# BUS.net
KiCad netlist of a schematic drawn in Altium Designer
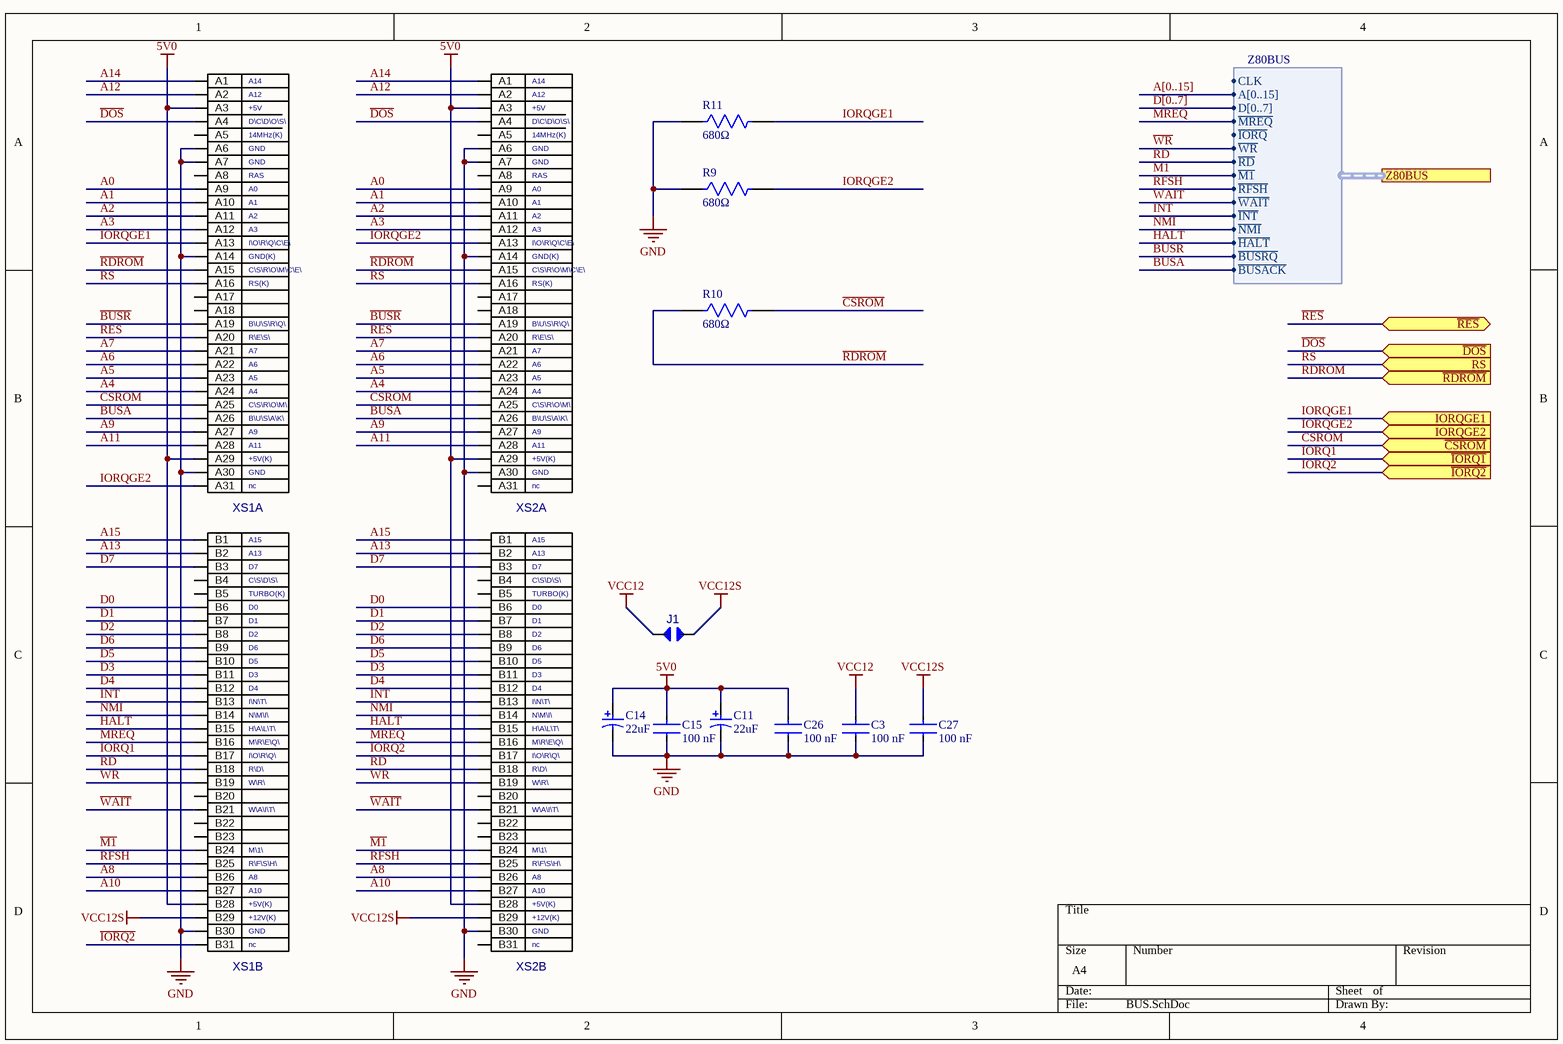
[diagram p0: BUS.SchDoc]

(export (version "E")
  (design (tool "Eeschema 10.0.6"))
  (components
    (comp (ref "C3")
      (value "CC0805KRX7R9BB104")
      (footprint "FP-CC0805-0_85-IPC_A")
      (description "CAP CER 0.1UF 50V X7R 0805")
      (fields (field (name "CAPACITANCE") "100 nF") (field (name "MANUFACTURER") "Yageo"))
      (libsource (lib "SchLib") (part "CMP-2100-03606-3"))
    )
    (comp (ref "C11")
      (value "TAJB226K016RNJ")
      (footprint "AVX-TAJ-B-2_M")
      (description "Standard Tantalum, 22 uF, +/- 10%, 16 V, -55 to 125 degC, 2-Pin SMD (1210), RoHS, Tape and Reel")
      (fields (field (name "CAPACITANCE") "22uF") (field (name "MANUFACTURER") "Kyocera AVX"))
      (libsource (lib "SchLib") (part "CMP-2100-03689-1"))
    )
    (comp (ref "C14")
      (value "TAJB226K016RNJ")
      (footprint "AVX-TAJ-B-2_M")
      (description "Standard Tantalum, 22 uF, +/- 10%, 16 V, -55 to 125 degC, 2-Pin SMD (1210), RoHS, Tape and Reel")
      (fields (field (name "CAPACITANCE") "22uF") (field (name "MANUFACTURER") "Kyocera AVX"))
      (libsource (lib "SchLib") (part "CMP-2100-03689-1"))
    )
    (comp (ref "C15")
      (value "CC0805KRX7R9BB104")
      (footprint "FP-CC0805-0_85-IPC_A")
      (description "CAP CER 0.1UF 50V X7R 0805")
      (fields (field (name "CAPACITANCE") "100 nF") (field (name "MANUFACTURER") "Yageo"))
      (libsource (lib "SchLib") (part "CMP-2100-03606-3"))
    )
    (comp (ref "C26")
      (value "CC0805KRX7R9BB104")
      (footprint "FP-CC0805-0_85-IPC_A")
      (description "CAP CER 0.1UF 50V X7R 0805")
      (fields (field (name "CAPACITANCE") "100 nF") (field (name "MANUFACTURER") "Yageo"))
      (libsource (lib "SchLib") (part "CMP-2100-03606-3"))
    )
    (comp (ref "C27")
      (value "CC0805KRX7R9BB104")
      (footprint "FP-CC0805-0_85-IPC_A")
      (description "CAP CER 0.1UF 50V X7R 0805")
      (fields (field (name "CAPACITANCE") "100 nF") (field (name "MANUFACTURER") "Yageo"))
      (libsource (lib "SchLib") (part "CMP-2100-03606-3"))
    )
    (comp (ref "J1")
      (value "JUMPER")
      (footprint "JUMPER_JUMPER(Primary)")
      (description "HLT->~IP")
      (libsource (lib "SchLib") (part "JUMPER"))
    )
    (comp (ref "R9")
      (value "680Ω")
      (footprint "FP-RT0805-IPC_A")
      (description "RES SMD 680 OHM 1% 1/8W 0805")
      (fields
        (field (name "MANUFACTURER") "Yageo")
        (field (name "MANUFACTURER PART NUMBER") "RT0805FRE07680RL")
      )
      (libsource (lib "SchLib") (part "CMP-03412-000082-1"))
    )
    (comp (ref "R10")
      (value "680Ω")
      (footprint "FP-RT0805-IPC_A")
      (description "RES SMD 680 OHM 1% 1/8W 0805")
      (fields
        (field (name "MANUFACTURER") "Yageo")
        (field (name "MANUFACTURER PART NUMBER") "RT0805FRE07680RL")
      )
      (libsource (lib "SchLib") (part "CMP-03412-000082-1"))
    )
    (comp (ref "R11")
      (value "680Ω")
      (footprint "FP-RT0805-IPC_A")
      (description "RES SMD 680 OHM 1% 1/8W 0805")
      (fields
        (field (name "MANUFACTURER") "Yageo")
        (field (name "MANUFACTURER PART NUMBER") "RT0805FRE07680RL")
      )
      (libsource (lib "SchLib") (part "CMP-03412-000082-1"))
    )
    (comp (ref "XS1")
      (value "ZXSLOT")
      (footprint "SLOT62_ZXSLOT(Primary)")
      (libsource (lib "SchLib") (part "ZXSLOT"))
    )
    (comp (ref "XS2")
      (value "ZXSLOT")
      (footprint "SLOT62_ZXSLOT(Primary)")
      (libsource (lib "SchLib") (part "ZXSLOT"))
    )
  )
  (nets
    (net (code "2") (name "/A0") (class "Default")
      (node (ref "XS1") (pin "A9") (pinfunction "A9_A9") (pintype "passive"))
      (node (ref "XS2") (pin "A9") (pinfunction "A9_A9") (pintype "passive"))
    )
    (net (code "3") (name "/A1") (class "Default")
      (node (ref "XS1") (pin "A10") (pinfunction "A10_A10") (pintype "passive"))
      (node (ref "XS2") (pin "A10") (pinfunction "A10_A10") (pintype "passive"))
    )
    (net (code "4") (name "/A2") (class "Default")
      (node (ref "XS1") (pin "A11") (pinfunction "A11_A11") (pintype "passive"))
      (node (ref "XS2") (pin "A11") (pinfunction "A11_A11") (pintype "passive"))
    )
    (net (code "5") (name "/A3") (class "Default")
      (node (ref "XS1") (pin "A12") (pinfunction "A12_A12") (pintype "passive"))
      (node (ref "XS2") (pin "A12") (pinfunction "A12_A12") (pintype "passive"))
    )
    (net (code "6") (name "/A4") (class "Default")
      (node (ref "XS1") (pin "A24") (pinfunction "A24_A24") (pintype "passive"))
      (node (ref "XS2") (pin "A24") (pinfunction "A24_A24") (pintype "passive"))
    )
    (net (code "7") (name "/A5") (class "Default")
      (node (ref "XS1") (pin "A23") (pinfunction "A23_A23") (pintype "passive"))
      (node (ref "XS2") (pin "A23") (pinfunction "A23_A23") (pintype "passive"))
    )
    (net (code "8") (name "/A6") (class "Default")
      (node (ref "XS1") (pin "A22") (pinfunction "A22_A22") (pintype "passive"))
      (node (ref "XS2") (pin "A22") (pinfunction "A22_A22") (pintype "passive"))
    )
    (net (code "9") (name "/A7") (class "Default")
      (node (ref "XS1") (pin "A21") (pinfunction "A21_A21") (pintype "passive"))
      (node (ref "XS2") (pin "A21") (pinfunction "A21_A21") (pintype "passive"))
    )
    (net (code "10") (name "/A8") (class "Default")
      (node (ref "XS1") (pin "B26") (pinfunction "B26_B26") (pintype "passive"))
      (node (ref "XS2") (pin "B26") (pinfunction "B26_B26") (pintype "passive"))
    )
    (net (code "11") (name "/A9") (class "Default")
      (node (ref "XS1") (pin "A27") (pinfunction "A27_A27") (pintype "passive"))
      (node (ref "XS2") (pin "A27") (pinfunction "A27_A27") (pintype "passive"))
    )
    (net (code "12") (name "/A10") (class "Default")
      (node (ref "XS1") (pin "B27") (pinfunction "B27_B27") (pintype "passive"))
      (node (ref "XS2") (pin "B27") (pinfunction "B27_B27") (pintype "passive"))
    )
    (net (code "13") (name "/A11") (class "Default")
      (node (ref "XS1") (pin "A28") (pinfunction "A28_A28") (pintype "passive"))
      (node (ref "XS2") (pin "A28") (pinfunction "A28_A28") (pintype "passive"))
    )
    (net (code "14") (name "/A12") (class "Default")
      (node (ref "XS1") (pin "A2") (pinfunction "A2_A2") (pintype "passive"))
      (node (ref "XS2") (pin "A2") (pinfunction "A2_A2") (pintype "passive"))
    )
    (net (code "15") (name "/A13") (class "Default")
      (node (ref "XS1") (pin "B2") (pinfunction "B2_B2") (pintype "passive"))
      (node (ref "XS2") (pin "B2") (pinfunction "B2_B2") (pintype "passive"))
    )
    (net (code "16") (name "/A14") (class "Default")
      (node (ref "XS1") (pin "A1") (pinfunction "A1_A1") (pintype "passive"))
      (node (ref "XS2") (pin "A1") (pinfunction "A1_A1") (pintype "passive"))
    )
    (net (code "17") (name "/A15") (class "Default")
      (node (ref "XS1") (pin "B1") (pinfunction "B1_B1") (pintype "passive"))
      (node (ref "XS2") (pin "B1") (pinfunction "B1_B1") (pintype "passive"))
    )
    (net (code "19") (name "/D0") (class "Default")
      (node (ref "XS1") (pin "B6") (pinfunction "B6_B6") (pintype "passive"))
      (node (ref "XS2") (pin "B6") (pinfunction "B6_B6") (pintype "passive"))
    )
    (net (code "20") (name "/D1") (class "Default")
      (node (ref "XS1") (pin "B7") (pinfunction "B7_B7") (pintype "passive"))
      (node (ref "XS2") (pin "B7") (pinfunction "B7_B7") (pintype "passive"))
    )
    (net (code "21") (name "/D2") (class "Default")
      (node (ref "XS1") (pin "B8") (pinfunction "B8_B8") (pintype "passive"))
      (node (ref "XS2") (pin "B8") (pinfunction "B8_B8") (pintype "passive"))
    )
    (net (code "22") (name "/D3") (class "Default")
      (node (ref "XS1") (pin "B11") (pinfunction "B11_B11") (pintype "passive"))
      (node (ref "XS2") (pin "B11") (pinfunction "B11_B11") (pintype "passive"))
    )
    (net (code "23") (name "/D4") (class "Default")
      (node (ref "XS1") (pin "B12") (pinfunction "B12_B12") (pintype "passive"))
      (node (ref "XS2") (pin "B12") (pinfunction "B12_B12") (pintype "passive"))
    )
    (net (code "24") (name "/D5") (class "Default")
      (node (ref "XS1") (pin "B10") (pinfunction "B10_B10") (pintype "passive"))
      (node (ref "XS2") (pin "B10") (pinfunction "B10_B10") (pintype "passive"))
    )
    (net (code "25") (name "/D6") (class "Default")
      (node (ref "XS1") (pin "B9") (pinfunction "B9_B9") (pintype "passive"))
      (node (ref "XS2") (pin "B9") (pinfunction "B9_B9") (pintype "passive"))
    )
    (net (code "26") (name "/D7") (class "Default")
      (node (ref "XS1") (pin "B3") (pinfunction "B3_B3") (pintype "passive"))
      (node (ref "XS2") (pin "B3") (pinfunction "B3_B3") (pintype "passive"))
    )
    (net (code "28") (name "/IORQGE1") (class "Default")
      (node (ref "R11") (pin "2") (pinfunction "2_2") (pintype "passive"))
      (node (ref "XS1") (pin "A13") (pinfunction "A13_A13") (pintype "passive"))
    )
    (net (code "29") (name "/IORQGE2") (class "Default")
      (node (ref "R9") (pin "2") (pinfunction "2_2") (pintype "passive"))
      (node (ref "XS1") (pin "A31") (pinfunction "A31_A31") (pintype "passive"))
      (node (ref "XS2") (pin "A13") (pinfunction "A13_A13") (pintype "passive"))
    )
    (net (code "30") (name "/RS") (class "Default")
      (node (ref "XS1") (pin "A16") (pinfunction "A16_A16") (pintype "passive"))
      (node (ref "XS2") (pin "A16") (pinfunction "A16_A16") (pintype "passive"))
    )
    (net (code "32") (name "/~{BUSA}") (class "Default")
      (node (ref "XS1") (pin "A26") (pinfunction "A26_A26") (pintype "passive"))
      (node (ref "XS2") (pin "A26") (pinfunction "A26_A26") (pintype "passive"))
    )
    (net (code "33") (name "/~{BUSR}") (class "Default")
      (node (ref "XS1") (pin "A19") (pinfunction "A19_A19") (pintype "passive"))
      (node (ref "XS2") (pin "A19") (pinfunction "A19_A19") (pintype "passive"))
    )
    (net (code "34") (name "/~{CSROM}") (class "Default")
      (node (ref "R10") (pin "2") (pinfunction "2_2") (pintype "passive"))
      (node (ref "XS1") (pin "A25") (pinfunction "A25_A25") (pintype "passive"))
      (node (ref "XS2") (pin "A25") (pinfunction "A25_A25") (pintype "passive"))
    )
    (net (code "35") (name "/~{DOS}") (class "Default")
      (node (ref "XS1") (pin "A4") (pinfunction "A4_A4") (pintype "passive"))
      (node (ref "XS2") (pin "A4") (pinfunction "A4_A4") (pintype "passive"))
    )
    (net (code "36") (name "/~{HALT}") (class "Default")
      (node (ref "XS1") (pin "B15") (pinfunction "B15_B15") (pintype "passive"))
      (node (ref "XS2") (pin "B15") (pinfunction "B15_B15") (pintype "passive"))
    )
    (net (code "37") (name "/~{INT}") (class "Default")
      (node (ref "XS1") (pin "B13") (pinfunction "B13_B13") (pintype "passive"))
      (node (ref "XS2") (pin "B13") (pinfunction "B13_B13") (pintype "passive"))
    )
    (net (code "38") (name "/~{IORQ1}") (class "Default")
      (node (ref "XS1") (pin "B17") (pinfunction "B17_B17") (pintype "passive"))
    )
    (net (code "39") (name "/~{IORQ2}") (class "Default")
      (node (ref "XS1") (pin "B31") (pinfunction "B31_B31") (pintype "passive"))
      (node (ref "XS2") (pin "B17") (pinfunction "B17_B17") (pintype "passive"))
    )
    (net (code "40") (name "/~{M1}") (class "Default")
      (node (ref "XS1") (pin "B24") (pinfunction "B24_B24") (pintype "passive"))
      (node (ref "XS2") (pin "B24") (pinfunction "B24_B24") (pintype "passive"))
    )
    (net (code "41") (name "/~{MREQ}") (class "Default")
      (node (ref "XS1") (pin "B16") (pinfunction "B16_B16") (pintype "passive"))
      (node (ref "XS2") (pin "B16") (pinfunction "B16_B16") (pintype "passive"))
    )
    (net (code "42") (name "/~{NMI}") (class "Default")
      (node (ref "XS1") (pin "B14") (pinfunction "B14_B14") (pintype "passive"))
      (node (ref "XS2") (pin "B14") (pinfunction "B14_B14") (pintype "passive"))
    )
    (net (code "43") (name "/~{RDROM}") (class "Default")
      (node (ref "R10") (pin "1") (pinfunction "1_1") (pintype "passive"))
      (node (ref "XS1") (pin "A15") (pinfunction "A15_A15") (pintype "passive"))
      (node (ref "XS2") (pin "A15") (pinfunction "A15_A15") (pintype "passive"))
    )
    (net (code "44") (name "/~{RD}") (class "Default")
      (node (ref "XS1") (pin "B18") (pinfunction "B18_B18") (pintype "passive"))
      (node (ref "XS2") (pin "B18") (pinfunction "B18_B18") (pintype "passive"))
    )
    (net (code "45") (name "/~{RES}") (class "Default")
      (node (ref "XS1") (pin "A20") (pinfunction "A20_A20") (pintype "passive"))
      (node (ref "XS2") (pin "A20") (pinfunction "A20_A20") (pintype "passive"))
    )
    (net (code "46") (name "/~{RFSH}") (class "Default")
      (node (ref "XS1") (pin "B25") (pinfunction "B25_B25") (pintype "passive"))
      (node (ref "XS2") (pin "B25") (pinfunction "B25_B25") (pintype "passive"))
    )
    (net (code "47") (name "/~{WAIT}") (class "Default")
      (node (ref "XS1") (pin "B21") (pinfunction "B21_B21") (pintype "passive"))
      (node (ref "XS2") (pin "B21") (pinfunction "B21_B21") (pintype "passive"))
    )
    (net (code "48") (name "/~{WR}") (class "Default")
      (node (ref "XS1") (pin "B19") (pinfunction "B19_B19") (pintype "passive"))
      (node (ref "XS2") (pin "B19") (pinfunction "B19_B19") (pintype "passive"))
    )
    (net (code "49") (name "5V0") (class "Default")
      (node (ref "C11") (pin "1") (pinfunction "1_1") (pintype "passive"))
      (node (ref "C14") (pin "1") (pinfunction "1_1") (pintype "passive"))
      (node (ref "C15") (pin "1") (pinfunction "1_1") (pintype "passive"))
      (node (ref "C26") (pin "1") (pinfunction "1_1") (pintype "passive"))
      (node (ref "XS1") (pin "A29") (pinfunction "A29_A29") (pintype "passive"))
      (node (ref "XS1") (pin "A3") (pinfunction "A3_A3") (pintype "passive"))
      (node (ref "XS1") (pin "B28") (pinfunction "B28_B28") (pintype "passive"))
      (node (ref "XS2") (pin "A29") (pinfunction "A29_A29") (pintype "passive"))
      (node (ref "XS2") (pin "A3") (pinfunction "A3_A3") (pintype "passive"))
      (node (ref "XS2") (pin "B28") (pinfunction "B28_B28") (pintype "passive"))
    )
    (net (code "50") (name "GND") (class "Default")
      (node (ref "C11") (pin "2") (pinfunction "2_2") (pintype "passive"))
      (node (ref "C14") (pin "2") (pinfunction "2_2") (pintype "passive"))
      (node (ref "C15") (pin "2") (pinfunction "2_2") (pintype "passive"))
      (node (ref "C26") (pin "2") (pinfunction "2_2") (pintype "passive"))
      (node (ref "C27") (pin "2") (pinfunction "2_2") (pintype "passive"))
      (node (ref "C3") (pin "2") (pinfunction "2_2") (pintype "passive"))
      (node (ref "R11") (pin "1") (pinfunction "1_1") (pintype "passive"))
      (node (ref "R9") (pin "1") (pinfunction "1_1") (pintype "passive"))
      (node (ref "XS1") (pin "A14") (pinfunction "A14_A14") (pintype "passive"))
      (node (ref "XS1") (pin "A30") (pinfunction "A30_A30") (pintype "passive"))
      (node (ref "XS1") (pin "A6") (pinfunction "A6_A6") (pintype "passive"))
      (node (ref "XS1") (pin "A7") (pinfunction "A7_A7") (pintype "passive"))
      (node (ref "XS1") (pin "B30") (pinfunction "B30_B30") (pintype "passive"))
      (node (ref "XS2") (pin "A14") (pinfunction "A14_A14") (pintype "passive"))
      (node (ref "XS2") (pin "A30") (pinfunction "A30_A30") (pintype "passive"))
      (node (ref "XS2") (pin "A6") (pinfunction "A6_A6") (pintype "passive"))
      (node (ref "XS2") (pin "A7") (pinfunction "A7_A7") (pintype "passive"))
      (node (ref "XS2") (pin "B30") (pinfunction "B30_B30") (pintype "passive"))
    )
    (net (code "51") (name "VCC12") (class "Default")
      (node (ref "C3") (pin "1") (pinfunction "1_1") (pintype "passive"))
      (node (ref "J1") (pin "0") (pinfunction "1_0") (pintype "passive"))
    )
    (net (code "52") (name "VCC12S") (class "Default")
      (node (ref "C27") (pin "1") (pinfunction "1_1") (pintype "passive"))
      (node (ref "J1") (pin "1") (pinfunction "2_1") (pintype "passive"))
      (node (ref "XS1") (pin "B29") (pinfunction "B29_B29") (pintype "passive"))
      (node (ref "XS2") (pin "B29") (pinfunction "B29_B29") (pintype "passive"))
    )
    (net (code "53") (name "unconnected-(XS1-PadA5)") (class "Default")
      (node (ref "XS1") (pin "A5") (pinfunction "A5_A5") (pintype "passive"))
    )
    (net (code "54") (name "unconnected-(XS1-PadA8)") (class "Default")
      (node (ref "XS1") (pin "A8") (pinfunction "A8_A8") (pintype "passive"))
    )
    (net (code "55") (name "unconnected-(XS1-PadA17)") (class "Default")
      (node (ref "XS1") (pin "A17") (pinfunction "A17_A17") (pintype "passive"))
    )
    (net (code "56") (name "unconnected-(XS1-PadA18)") (class "Default")
      (node (ref "XS1") (pin "A18") (pinfunction "A18_A18") (pintype "passive"))
    )
    (net (code "57") (name "unconnected-(XS1-PadB4)") (class "Default")
      (node (ref "XS1") (pin "B4") (pinfunction "B4_B4") (pintype "passive"))
    )
    (net (code "58") (name "unconnected-(XS1-PadB5)") (class "Default")
      (node (ref "XS1") (pin "B5") (pinfunction "B5_B5") (pintype "passive"))
    )
    (net (code "59") (name "unconnected-(XS1-PadB20)") (class "Default")
      (node (ref "XS1") (pin "B20") (pinfunction "B20_B20") (pintype "passive"))
    )
    (net (code "60") (name "unconnected-(XS1-PadB22)") (class "Default")
      (node (ref "XS1") (pin "B22") (pinfunction "B22_B22") (pintype "passive"))
    )
    (net (code "61") (name "unconnected-(XS1-PadB23)") (class "Default")
      (node (ref "XS1") (pin "B23") (pinfunction "B23_B23") (pintype "passive"))
    )
    (net (code "62") (name "unconnected-(XS2-PadA5)") (class "Default")
      (node (ref "XS2") (pin "A5") (pinfunction "A5_A5") (pintype "passive"))
    )
    (net (code "63") (name "unconnected-(XS2-PadA8)") (class "Default")
      (node (ref "XS2") (pin "A8") (pinfunction "A8_A8") (pintype "passive"))
    )
    (net (code "64") (name "unconnected-(XS2-PadA17)") (class "Default")
      (node (ref "XS2") (pin "A17") (pinfunction "A17_A17") (pintype "passive"))
    )
    (net (code "65") (name "unconnected-(XS2-PadA18)") (class "Default")
      (node (ref "XS2") (pin "A18") (pinfunction "A18_A18") (pintype "passive"))
    )
    (net (code "66") (name "unconnected-(XS2-PadA31)") (class "Default")
      (node (ref "XS2") (pin "A31") (pinfunction "A31_A31") (pintype "passive"))
    )
    (net (code "67") (name "unconnected-(XS2-PadB4)") (class "Default")
      (node (ref "XS2") (pin "B4") (pinfunction "B4_B4") (pintype "passive"))
    )
    (net (code "68") (name "unconnected-(XS2-PadB5)") (class "Default")
      (node (ref "XS2") (pin "B5") (pinfunction "B5_B5") (pintype "passive"))
    )
    (net (code "69") (name "unconnected-(XS2-PadB20)") (class "Default")
      (node (ref "XS2") (pin "B20") (pinfunction "B20_B20") (pintype "passive"))
    )
    (net (code "70") (name "unconnected-(XS2-PadB22)") (class "Default")
      (node (ref "XS2") (pin "B22") (pinfunction "B22_B22") (pintype "passive"))
    )
    (net (code "71") (name "unconnected-(XS2-PadB23)") (class "Default")
      (node (ref "XS2") (pin "B23") (pinfunction "B23_B23") (pintype "passive"))
    )
    (net (code "72") (name "unconnected-(XS2-PadB31)") (class "Default")
      (node (ref "XS2") (pin "B31") (pinfunction "B31_B31") (pintype "passive"))
    )
  )
)
